# breakouts.net
KiCad netlist of a schematic drawn in EAGLE
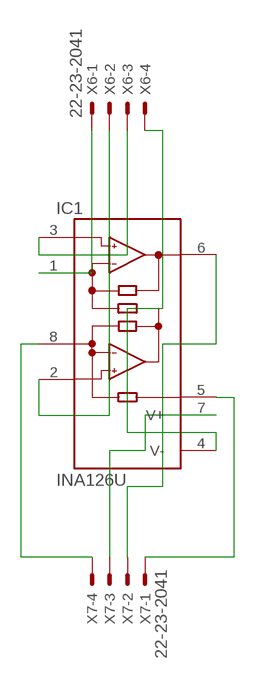
[diagram p0: schematic, sheet 1]

(export (version "E")
  (design (tool "Eeschema 10.0.6"))
  (components
    (comp (ref "IC1")
      (value "INA126U")
      (footprint "eagle-import:SO08")
      (fields (field (name "MF") "Texas Instruments") (field (name "MP") "INA126"))
      (libsource (lib "eagle-import") (part "INA126U"))
    )
    (comp (ref "X6")
      (value "22-23-2041")
      (footprint "eagle-import:22-23-2041")
      (fields (field (name "MF") "MOLEX"))
      (libsource (lib "eagle-import") (part "22-23-2041"))
    )
    (comp (ref "X7")
      (value "22-23-2041")
      (footprint "eagle-import:22-23-2041")
      (fields (field (name "MF") "MOLEX"))
      (libsource (lib "eagle-import") (part "22-23-2041"))
    )
  )
  (nets
    (net (code "1") (name "Net-(IC1-+IN)") (class "Default")
      (node (ref "IC1") (pin "3") (pinfunction "+IN_3") (pintype "input"))
      (node (ref "X6") (pin "3") (pinfunction "S_3") (pintype "passive"))
    )
    (net (code "2") (name "Net-(IC1--IN)") (class "Default")
      (node (ref "IC1") (pin "2") (pinfunction "-IN_2") (pintype "input"))
      (node (ref "X6") (pin "2") (pinfunction "S_2") (pintype "passive"))
    )
    (net (code "3") (name "Net-(IC1-OUT)") (class "Default")
      (node (ref "IC1") (pin "6") (pinfunction "OUT_6") (pintype "output"))
      (node (ref "X7") (pin "2") (pinfunction "S_2") (pintype "passive"))
    )
    (net (code "4") (name "Net-(IC1-REF)") (class "Default")
      (node (ref "IC1") (pin "5") (pinfunction "REF_5") (pintype "passive"))
      (node (ref "X7") (pin "1") (pinfunction "S_1") (pintype "passive"))
    )
    (net (code "5") (name "Net-(IC1-V+)") (class "Default")
      (node (ref "IC1") (pin "7") (pinfunction "V+_7") (pintype "power_in"))
      (node (ref "X7") (pin "3") (pinfunction "S_3") (pintype "passive"))
    )
    (net (code "6") (name "Net-(IC1-V-)") (class "Default")
      (node (ref "IC1") (pin "4") (pinfunction "V-_4") (pintype "power_in"))
      (node (ref "X6") (pin "4") (pinfunction "S_4") (pintype "passive"))
    )
    (net (code "7") (name "Net-(X6A-S)") (class "Default")
      (node (ref "IC1") (pin "1") (pinfunction "RG_1") (pintype "passive"))
      (node (ref "X6") (pin "1") (pinfunction "S_1") (pintype "passive"))
    )
    (net (code "8") (name "Net-(X7D-S)") (class "Default")
      (node (ref "IC1") (pin "8") (pinfunction "RG_8") (pintype "passive"))
      (node (ref "X7") (pin "4") (pinfunction "S_4") (pintype "passive"))
    )
  )
)
